# esp8266-hw9.net
KiCad netlist of a schematic drawn in EAGLE
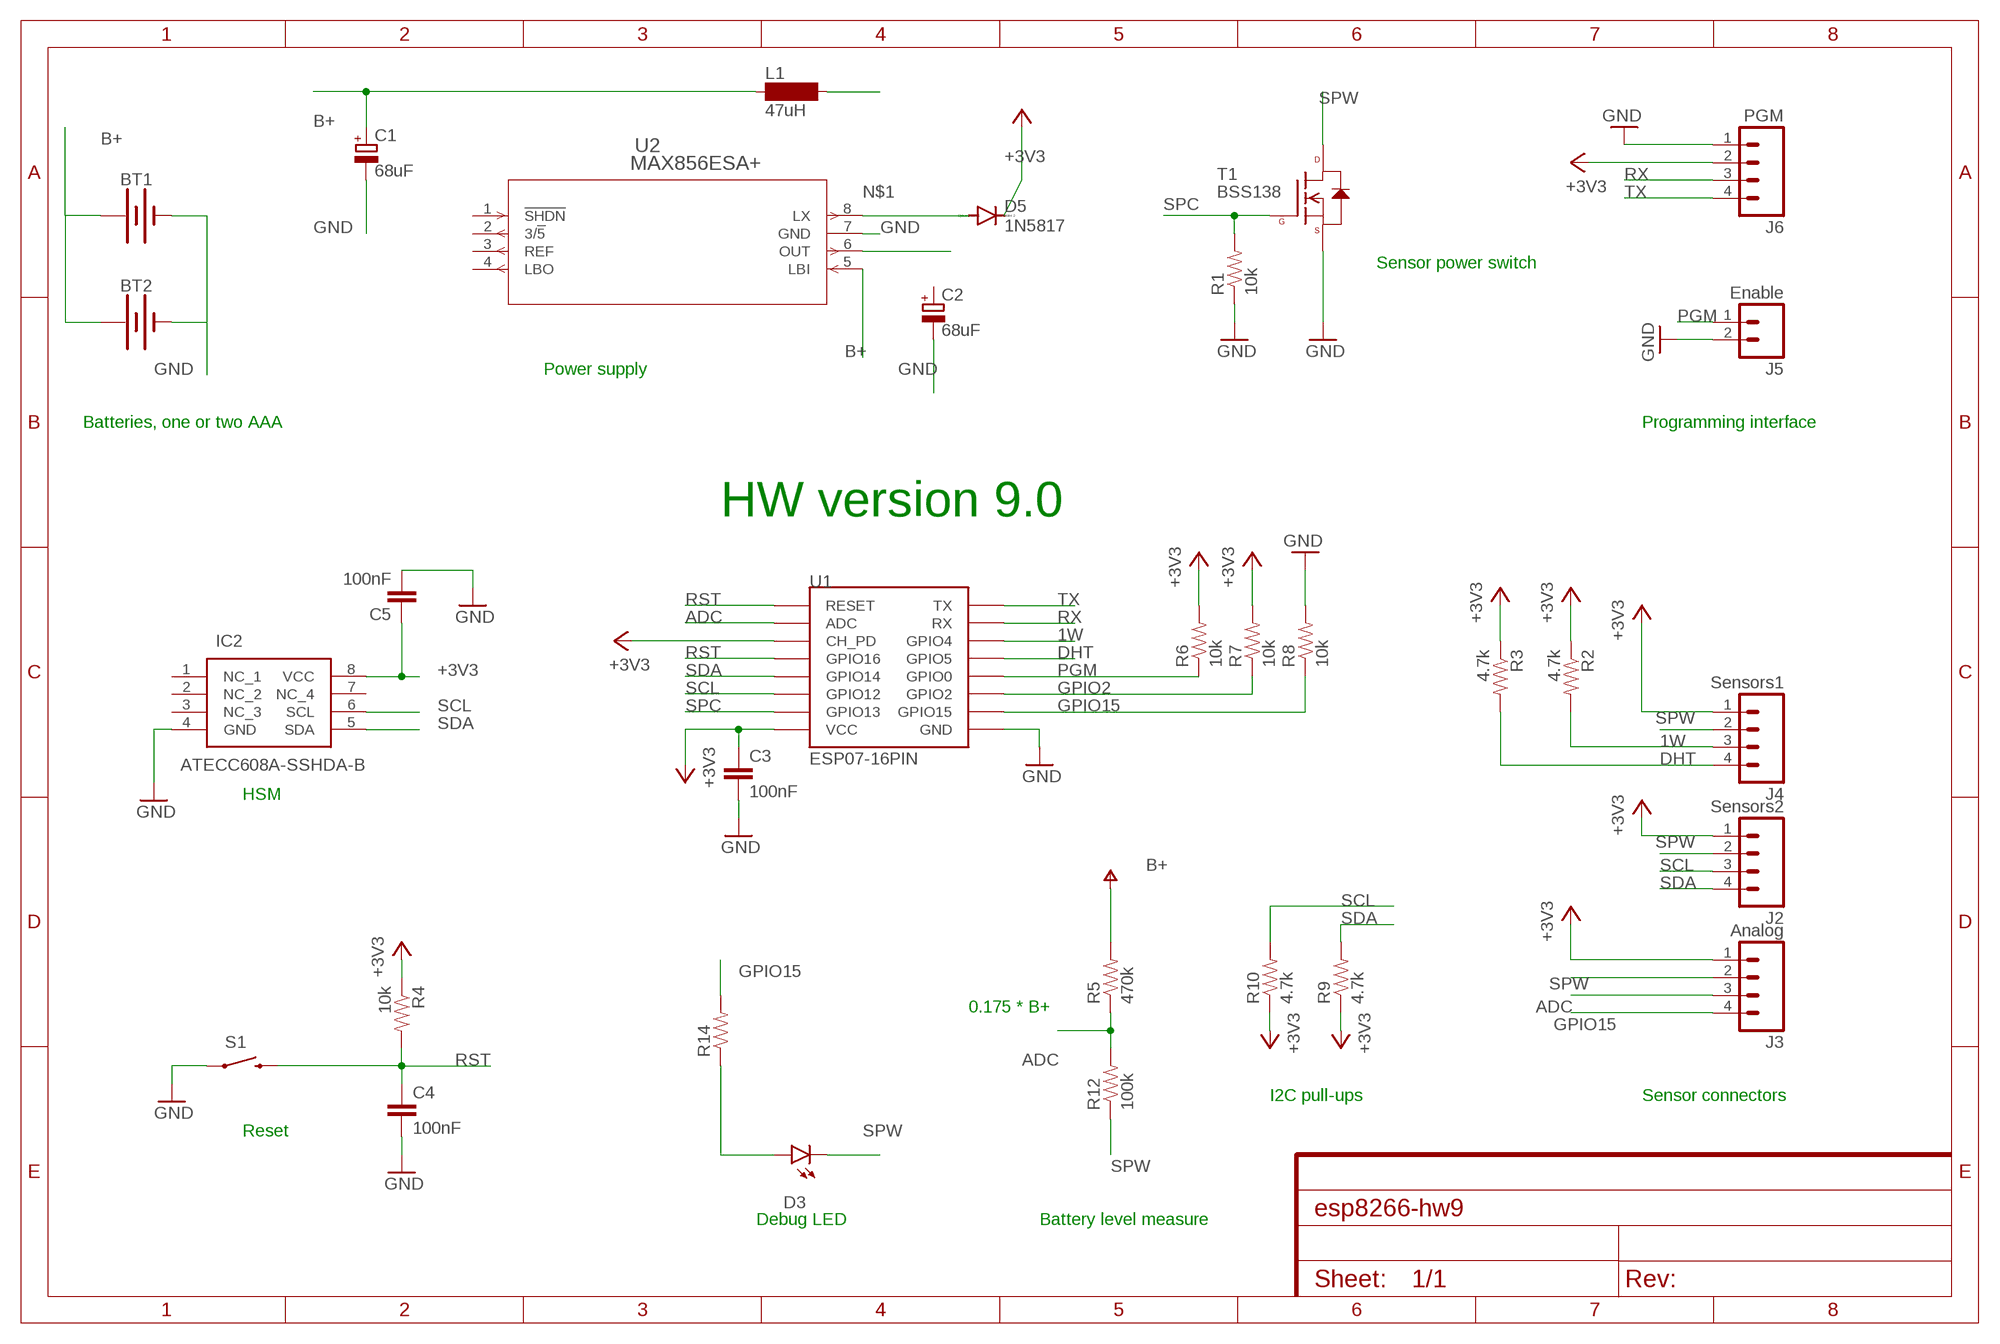
[diagram p0: schematic, sheet 1]

(export (version "E")
  (design (tool "Eeschema 10.0.6"))
  (components
    (comp (ref "BT1")
      (value "BATTERY-AAA")
      (footprint "eagle-import:BATTERY-AAA")
      (libsource (lib "eagle-import") (part "BATTERY-AAA"))
    )
    (comp (ref "BT2")
      (value "BATTERY-AAA")
      (footprint "eagle-import:BATTERY-AAA")
      (libsource (lib "eagle-import") (part "BATTERY-AAA"))
    )
    (comp (ref "C1")
      (value "68uF")
      (footprint "eagle-import:E2,5-6")
      (libsource (lib "eagle-import") (part "CPOL-EUE2.5-6"))
    )
    (comp (ref "C2")
      (value "68uF")
      (footprint "eagle-import:E2,5-6")
      (libsource (lib "eagle-import") (part "CPOL-EUE2.5-6"))
    )
    (comp (ref "C3")
      (value "100nF")
      (footprint "eagle-import:0805")
      (libsource (lib "eagle-import") (part "CAP0805"))
    )
    (comp (ref "C4")
      (value "100nF")
      (footprint "eagle-import:0805")
      (libsource (lib "eagle-import") (part "CAP0805"))
    )
    (comp (ref "C5")
      (value "100nF")
      (footprint "eagle-import:0805")
      (libsource (lib "eagle-import") (part "CAP0805"))
    )
    (comp (ref "D3")
      (value "LED3MM")
      (footprint "eagle-import:LED_3MM")
      (libsource (lib "eagle-import") (part "LED3MM"))
    )
    (comp (ref "D5")
      (value "1N5817")
      (footprint "eagle-import:DO41-10")
      (libsource (lib "eagle-import") (part "DIODE-DO41-10"))
    )
    (comp (ref "IC2")
      (value "ATECC608A-SSHDA-B")
      (footprint "eagle-import:SOIC127P600X175-8N")
      (fields (field (name "MOUSER_PART_NUMBER") "556-ATECC608ASSHDAB"))
      (libsource (lib "eagle-import") (part "ATECC608A-SSHDA-B"))
    )
    (comp (ref "J2")
      (value "Sensors2")
      (footprint "eagle-import:1X04")
      (libsource (lib "eagle-import") (part "M04PTH"))
    )
    (comp (ref "J3")
      (value "Analog")
      (footprint "eagle-import:1X04")
      (libsource (lib "eagle-import") (part "M04PTH"))
    )
    (comp (ref "J4")
      (value "Sensors1")
      (footprint "eagle-import:1X04")
      (libsource (lib "eagle-import") (part "M04PTH"))
    )
    (comp (ref "J5")
      (value "Enable")
      (footprint "eagle-import:1X02")
      (libsource (lib "eagle-import") (part "M02PTH"))
    )
    (comp (ref "J6")
      (value "PGM")
      (footprint "eagle-import:1X04")
      (libsource (lib "eagle-import") (part "M04PTH"))
    )
    (comp (ref "L1")
      (value "47uH")
      (footprint "eagle-import:SM-1206")
      (libsource (lib "eagle-import") (part "SM-1206"))
    )
    (comp (ref "R1")
      (value "10k")
      (footprint "eagle-import:0805")
      (libsource (lib "eagle-import") (part "RESISTOR0805-RES"))
    )
    (comp (ref "R2")
      (value "4.7k")
      (footprint "eagle-import:0805")
      (libsource (lib "eagle-import") (part "RESISTOR0805-RES"))
    )
    (comp (ref "R3")
      (value "4.7k")
      (footprint "eagle-import:0805")
      (libsource (lib "eagle-import") (part "RESISTOR0805-RES"))
    )
    (comp (ref "R4")
      (value "10k")
      (footprint "eagle-import:0805")
      (libsource (lib "eagle-import") (part "RESISTOR0805-RES"))
    )
    (comp (ref "R5")
      (value "470k")
      (footprint "eagle-import:0805")
      (libsource (lib "eagle-import") (part "RESISTOR0805-RES"))
    )
    (comp (ref "R6")
      (value "10k")
      (footprint "eagle-import:0805")
      (libsource (lib "eagle-import") (part "RESISTOR0805-RES"))
    )
    (comp (ref "R7")
      (value "10k")
      (footprint "eagle-import:0805")
      (libsource (lib "eagle-import") (part "RESISTOR0805-RES"))
    )
    (comp (ref "R8")
      (value "10k")
      (footprint "eagle-import:0805")
      (libsource (lib "eagle-import") (part "RESISTOR0805-RES"))
    )
    (comp (ref "R9")
      (value "4.7k")
      (footprint "eagle-import:0805")
      (libsource (lib "eagle-import") (part "RESISTOR0805-RES"))
    )
    (comp (ref "R10")
      (value "4.7k")
      (footprint "eagle-import:0805")
      (libsource (lib "eagle-import") (part "RESISTOR0805-RES"))
    )
    (comp (ref "R12")
      (value "100k")
      (footprint "eagle-import:0805")
      (libsource (lib "eagle-import") (part "RESISTOR0805-RES"))
    )
    (comp (ref "R14")
      (value "470")
      (footprint "eagle-import:0805")
      (libsource (lib "eagle-import") (part "RESISTOR0805-RES"))
    )
    (comp (ref "S1")
      (value "RESET")
      (footprint "eagle-import:TACTILE-SWITCH-1101NE")
      (libsource (lib "eagle-import") (part "SWITCH-MOMENTARY-2SMD-1101NE"))
    )
    (comp (ref "T1")
      (value "BSS138")
      (footprint "eagle-import:SOT23-3")
      (libsource (lib "eagle-import") (part "N-CHANNEL-MOSFET-BSS138"))
    )
    (comp (ref "U1")
      (value "ESP07-16PIN")
      (footprint "eagle-import:ESP07-16PIN")
      (libsource (lib "eagle-import") (part "ESP07-16PIN"))
    )
    (comp (ref "U2")
      (value "MAX856ESA+")
      (footprint "eagle-import:21-0041B_8")
      (libsource (lib "eagle-import") (part "MAX856ESA+"))
    )
  )
  (nets
    (net (code "1") (name "+3V3") (class "Default")
      (node (ref "C3") (pin "1") (pinfunction "1_1") (pintype "passive"))
      (node (ref "C5") (pin "1") (pinfunction "1_1") (pintype "passive"))
      (node (ref "D5") (pin "C") (pinfunction "C_C") (pintype "passive"))
      (node (ref "IC2") (pin "8") (pinfunction "VCC_8") (pintype "bidirectional"))
      (node (ref "J2") (pin "1") (pinfunction "1_1") (pintype "passive"))
      (node (ref "J3") (pin "1") (pinfunction "1_1") (pintype "passive"))
      (node (ref "J4") (pin "1") (pinfunction "1_1") (pintype "passive"))
      (node (ref "J6") (pin "2") (pinfunction "2_2") (pintype "passive"))
      (node (ref "R10") (pin "1") (pinfunction "1_1") (pintype "passive"))
      (node (ref "R2") (pin "1") (pinfunction "1_1") (pintype "passive"))
      (node (ref "R3") (pin "1") (pinfunction "1_1") (pintype "passive"))
      (node (ref "R4") (pin "1") (pinfunction "1_1") (pintype "passive"))
      (node (ref "R6") (pin "2") (pinfunction "2_2") (pintype "passive"))
      (node (ref "R7") (pin "2") (pinfunction "2_2") (pintype "passive"))
      (node (ref "R9") (pin "1") (pinfunction "1_1") (pintype "passive"))
      (node (ref "U1") (pin "CH_PD") (pinfunction "CH_PD_CH_PD") (pintype "bidirectional"))
      (node (ref "U1") (pin "VCC") (pinfunction "VCC_VCC") (pintype "bidirectional"))
    )
    (net (code "2") (name "/1W") (class "Default")
      (node (ref "J4") (pin "3") (pinfunction "3_3") (pintype "passive"))
      (node (ref "R2") (pin "2") (pinfunction "2_2") (pintype "passive"))
      (node (ref "U1") (pin "GPIO4") (pinfunction "GPIO4_GPIO4") (pintype "bidirectional"))
    )
    (net (code "3") (name "/ADC") (class "Default")
      (node (ref "J3") (pin "3") (pinfunction "3_3") (pintype "passive"))
      (node (ref "R12") (pin "2") (pinfunction "2_2") (pintype "passive"))
      (node (ref "R5") (pin "1") (pinfunction "1_1") (pintype "passive"))
      (node (ref "U1") (pin "ADC") (pinfunction "ADC_ADC") (pintype "bidirectional"))
    )
    (net (code "4") (name "/DHT") (class "Default")
      (node (ref "J4") (pin "4") (pinfunction "4_4") (pintype "passive"))
      (node (ref "R3") (pin "2") (pinfunction "2_2") (pintype "passive"))
      (node (ref "U1") (pin "GPIO5") (pinfunction "GPIO5_GPIO5") (pintype "bidirectional"))
    )
    (net (code "5") (name "/GPIO2") (class "Default")
      (node (ref "R7") (pin "1") (pinfunction "1_1") (pintype "passive"))
      (node (ref "U1") (pin "GPIO2") (pinfunction "GPIO2_GPIO2") (pintype "bidirectional"))
    )
    (net (code "6") (name "/GPIO15") (class "Default")
      (node (ref "J3") (pin "4") (pinfunction "4_4") (pintype "passive"))
      (node (ref "R14") (pin "2") (pinfunction "2_2") (pintype "passive"))
      (node (ref "R8") (pin "1") (pinfunction "1_1") (pintype "passive"))
      (node (ref "U1") (pin "GPIO15") (pinfunction "GPIO15_GPIO15") (pintype "bidirectional"))
    )
    (net (code "7") (name "/N$1") (class "Default")
      (node (ref "D5") (pin "A") (pinfunction "A_A") (pintype "passive"))
      (node (ref "U2") (pin "8") (pinfunction "LX_8") (pintype "output"))
    )
    (net (code "8") (name "/PGM") (class "Default")
      (node (ref "J5") (pin "1") (pinfunction "1_1") (pintype "passive"))
      (node (ref "R6") (pin "1") (pinfunction "1_1") (pintype "passive"))
      (node (ref "U1") (pin "GPIO0") (pinfunction "GPIO0_GPIO0") (pintype "bidirectional"))
    )
    (net (code "9") (name "/RST") (class "Default")
      (node (ref "C4") (pin "1") (pinfunction "1_1") (pintype "passive"))
      (node (ref "R4") (pin "2") (pinfunction "2_2") (pintype "passive"))
      (node (ref "S1") (pin "2") (pinfunction "2_2") (pintype "passive"))
      (node (ref "U1") (pin "GPIO16") (pinfunction "GPIO16_GPIO16") (pintype "bidirectional"))
      (node (ref "U1") (pin "REST") (pinfunction "RESET_REST") (pintype "bidirectional"))
    )
    (net (code "10") (name "/RX") (class "Default")
      (node (ref "J6") (pin "3") (pinfunction "3_3") (pintype "passive"))
      (node (ref "U1") (pin "RX") (pinfunction "RX_RX") (pintype "bidirectional"))
    )
    (net (code "11") (name "/SCL") (class "Default")
      (node (ref "IC2") (pin "6") (pinfunction "SCL_6") (pintype "bidirectional"))
      (node (ref "J2") (pin "3") (pinfunction "3_3") (pintype "passive"))
      (node (ref "R10") (pin "2") (pinfunction "2_2") (pintype "passive"))
      (node (ref "U1") (pin "GPIO12") (pinfunction "GPIO12_GPIO12") (pintype "bidirectional"))
    )
    (net (code "12") (name "/SDA") (class "Default")
      (node (ref "IC2") (pin "5") (pinfunction "SDA_5") (pintype "bidirectional"))
      (node (ref "J2") (pin "4") (pinfunction "4_4") (pintype "passive"))
      (node (ref "R9") (pin "2") (pinfunction "2_2") (pintype "passive"))
      (node (ref "U1") (pin "GPIO14") (pinfunction "GPIO14_GPIO14") (pintype "bidirectional"))
    )
    (net (code "13") (name "/SPC") (class "Default")
      (node (ref "R1") (pin "2") (pinfunction "2_2") (pintype "passive"))
      (node (ref "T1") (pin "1") (pinfunction "G_1") (pintype "passive"))
      (node (ref "U1") (pin "GPIO13") (pinfunction "GPIO13_GPIO13") (pintype "bidirectional"))
    )
    (net (code "14") (name "/SPW") (class "Default")
      (node (ref "D3") (pin "K") (pinfunction "C_K") (pintype "passive"))
      (node (ref "J2") (pin "2") (pinfunction "2_2") (pintype "passive"))
      (node (ref "J3") (pin "2") (pinfunction "2_2") (pintype "passive"))
      (node (ref "J4") (pin "2") (pinfunction "2_2") (pintype "passive"))
      (node (ref "R12") (pin "1") (pinfunction "1_1") (pintype "passive"))
      (node (ref "T1") (pin "3") (pinfunction "D_3") (pintype "passive"))
    )
    (net (code "15") (name "/TX") (class "Default")
      (node (ref "J6") (pin "4") (pinfunction "4_4") (pintype "passive"))
      (node (ref "U1") (pin "TX") (pinfunction "TX_TX") (pintype "bidirectional"))
    )
    (net (code "16") (name "GND") (class "Default")
      (node (ref "BT1") (pin "GND@1") (pinfunction "-_GND@1") (pintype "power_in"))
      (node (ref "BT2") (pin "GND@1") (pinfunction "-_GND@1") (pintype "power_in"))
      (node (ref "C1") (pin "-") (pinfunction "-_-") (pintype "passive"))
      (node (ref "C2") (pin "-") (pinfunction "-_-") (pintype "passive"))
      (node (ref "C3") (pin "2") (pinfunction "2_2") (pintype "passive"))
      (node (ref "C4") (pin "2") (pinfunction "2_2") (pintype "passive"))
      (node (ref "C5") (pin "2") (pinfunction "2_2") (pintype "passive"))
      (node (ref "IC2") (pin "4") (pinfunction "GND_4") (pintype "bidirectional"))
      (node (ref "J5") (pin "2") (pinfunction "2_2") (pintype "passive"))
      (node (ref "J6") (pin "1") (pinfunction "1_1") (pintype "passive"))
      (node (ref "R1") (pin "1") (pinfunction "1_1") (pintype "passive"))
      (node (ref "R8") (pin "2") (pinfunction "2_2") (pintype "passive"))
      (node (ref "S1") (pin "1") (pinfunction "1_1") (pintype "passive"))
      (node (ref "T1") (pin "2") (pinfunction "S_2") (pintype "passive"))
      (node (ref "U1") (pin "GND") (pinfunction "GND_GND") (pintype "bidirectional"))
      (node (ref "U2") (pin "7") (pinfunction "GND_7") (pintype "power_in"))
    )
    (net (code "17") (name "Net-(D3-PadA)") (class "Default")
      (node (ref "D3") (pin "A") (pinfunction "A_A") (pintype "passive"))
      (node (ref "R14") (pin "1") (pinfunction "1_1") (pintype "passive"))
    )
    (net (code "18") (name "V+") (class "Default")
      (node (ref "BT1") (pin "PWR@1") (pinfunction "+_PWR@1") (pintype "power_in"))
      (node (ref "BT2") (pin "PWR@1") (pinfunction "+_PWR@1") (pintype "power_in"))
      (node (ref "C1") (pin "+") (pinfunction "+_+") (pintype "passive"))
      (node (ref "L1") (pin "1") (pinfunction "1_1") (pintype "passive"))
      (node (ref "R5") (pin "2") (pinfunction "2_2") (pintype "passive"))
      (node (ref "U2") (pin "5") (pinfunction "LBI_5") (pintype "input"))
    )
    (net (code "19") (name "unconnected-(C2-Pad+)") (class "Default")
      (node (ref "C2") (pin "+") (pinfunction "+_+") (pintype "passive"))
    )
    (net (code "20") (name "unconnected-(IC2-NC_1-Pad1)") (class "Default")
      (node (ref "IC2") (pin "1") (pinfunction "NC_1_1") (pintype "bidirectional"))
    )
    (net (code "21") (name "unconnected-(IC2-NC_2-Pad2)") (class "Default")
      (node (ref "IC2") (pin "2") (pinfunction "NC_2_2") (pintype "bidirectional"))
    )
    (net (code "22") (name "unconnected-(IC2-NC_3-Pad3)") (class "Default")
      (node (ref "IC2") (pin "3") (pinfunction "NC_3_3") (pintype "bidirectional"))
    )
    (net (code "23") (name "unconnected-(IC2-NC_4-Pad7)") (class "Default")
      (node (ref "IC2") (pin "7") (pinfunction "NC_4_7") (pintype "bidirectional"))
    )
    (net (code "24") (name "unconnected-(L1-Pad2)") (class "Default")
      (node (ref "L1") (pin "2") (pinfunction "2_2") (pintype "passive"))
    )
    (net (code "25") (name "unconnected-(U2-3{slash}~{5}-Pad2)") (class "Default")
      (node (ref "U2") (pin "2") (pinfunction "3/~{5}_2") (pintype "output"))
    )
    (net (code "26") (name "unconnected-(U2-LBO-Pad4)") (class "Default")
      (node (ref "U2") (pin "4") (pinfunction "LBO_4") (pintype "output"))
    )
    (net (code "27") (name "unconnected-(U2-OUT-Pad6)") (class "Default")
      (node (ref "U2") (pin "6") (pinfunction "OUT_6") (pintype "output"))
    )
    (net (code "28") (name "unconnected-(U2-REF-Pad3)") (class "Default")
      (node (ref "U2") (pin "3") (pinfunction "REF_3") (pintype "output"))
    )
    (net (code "29") (name "unconnected-(U2-~{SHDN}-Pad1)") (class "Default")
      (node (ref "U2") (pin "1") (pinfunction "~{SHDN}_1") (pintype "input"))
    )
  )
)
